# 74.net
KiCad netlist of a schematic drawn in EAGLE
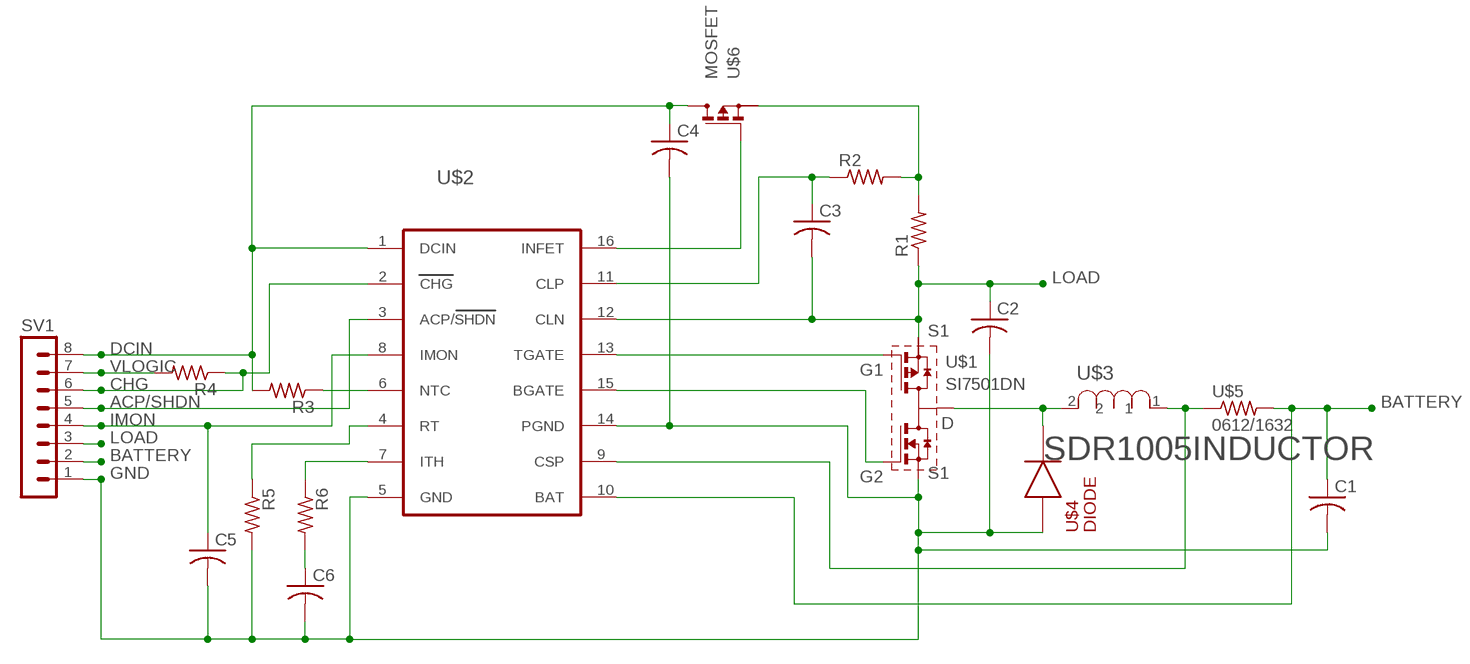
[diagram p0: schematic, sheet 1]

(export (version "E")
  (design (tool "Eeschema 10.0.6"))
  (components
    (comp (ref "C1")
      (value "C-USC1210")
      (footprint "eagle-import:C1210")
      (libsource (lib "eagle-import") (part "C-USC1210"))
    )
    (comp (ref "C2")
      (value "C-USC1210")
      (footprint "eagle-import:C1210")
      (libsource (lib "eagle-import") (part "C-USC1210"))
    )
    (comp (ref "C3")
      (value "C-USC1210")
      (footprint "eagle-import:C1210")
      (libsource (lib "eagle-import") (part "C-USC1210"))
    )
    (comp (ref "C4")
      (value "C-USC1210")
      (footprint "eagle-import:C1210")
      (libsource (lib "eagle-import") (part "C-USC1210"))
    )
    (comp (ref "C5")
      (value "C-USC1210")
      (footprint "eagle-import:C1210")
      (libsource (lib "eagle-import") (part "C-USC1210"))
    )
    (comp (ref "C6")
      (value "C-USC1210")
      (footprint "eagle-import:C1210")
      (libsource (lib "eagle-import") (part "C-USC1210"))
    )
    (comp (ref "R1")
      (value "R-US_R1206")
      (footprint "eagle-import:R1206")
      (libsource (lib "eagle-import") (part "R-US_R1206"))
    )
    (comp (ref "R2")
      (value "R-US_R1206")
      (footprint "eagle-import:R1206")
      (libsource (lib "eagle-import") (part "R-US_R1206"))
    )
    (comp (ref "R3")
      (value "R-US_R1206")
      (footprint "eagle-import:R1206")
      (libsource (lib "eagle-import") (part "R-US_R1206"))
    )
    (comp (ref "R4")
      (value "R-US_R1206")
      (footprint "eagle-import:R1206")
      (libsource (lib "eagle-import") (part "R-US_R1206"))
    )
    (comp (ref "R5")
      (value "R-US_R1206")
      (footprint "eagle-import:R1206")
      (libsource (lib "eagle-import") (part "R-US_R1206"))
    )
    (comp (ref "R6")
      (value "R-US_R1206")
      (footprint "eagle-import:R1206")
      (libsource (lib "eagle-import") (part "R-US_R1206"))
    )
    (comp (ref "SV1")
      (value "MA08-1")
      (footprint "eagle-import:MA08-1")
      (libsource (lib "eagle-import") (part "MA08-1"))
    )
    (comp (ref "U$1")
      (value "SI7501DN")
      (footprint "eagle-import:POWERPAK")
      (libsource (lib "eagle-import") (part "SI7501DN"))
    )
    (comp (ref "U$2")
      (value "LTC6004")
      (footprint "eagle-import:SSOP-16")
      (libsource (lib "eagle-import") (part "LTC6004"))
    )
    (comp (ref "U$3")
      (value "SDR1005INDUCTOR")
      (footprint "eagle-import:POWERINDUCTOR")
      (libsource (lib "eagle-import") (part "SDR1005INDUCTOR"))
    )
    (comp (ref "U$4")
      (value "DIODE")
      (footprint "eagle-import:DIODE")
      (libsource (lib "eagle-import") (part "DIODE"))
    )
    (comp (ref "U$5")
      (value "0612/1632")
      (footprint "eagle-import:0612_1632")
      (libsource (lib "eagle-import") (part "0612/1632"))
    )
    (comp (ref "U$6")
      (value "MOSFET")
      (footprint "eagle-import:SOT-23")
      (libsource (lib "eagle-import") (part "MOSFET"))
    )
  )
  (nets
    (net (code "1") (name "/ACP{slash}SHDN") (class "Default")
      (node (ref "SV1") (pin "5") (pinfunction "5_5") (pintype "passive"))
      (node (ref "U$2") (pin "3") (pinfunction "ACP/SHDN_3") (pintype "power_in"))
    )
    (net (code "2") (name "/BATTERY") (class "Default")
      (node (ref "C1") (pin "1") (pinfunction "1_1") (pintype "passive"))
      (node (ref "SV1") (pin "2") (pinfunction "2_2") (pintype "passive"))
      (node (ref "U$2") (pin "10") (pinfunction "BAT_10") (pintype "power_in"))
      (node (ref "U$5") (pin "2") (pinfunction "2_2") (pintype "passive"))
    )
    (net (code "3") (name "/CHG") (class "Default")
      (node (ref "R4") (pin "1") (pinfunction "1_1") (pintype "passive"))
      (node (ref "SV1") (pin "6") (pinfunction "6_6") (pintype "passive"))
      (node (ref "U$2") (pin "2") (pinfunction "CHG_2") (pintype "power_in"))
    )
    (net (code "4") (name "/DCIN") (class "Default")
      (node (ref "C4") (pin "1") (pinfunction "1_1") (pintype "passive"))
      (node (ref "R3") (pin "2") (pinfunction "2_2") (pintype "passive"))
      (node (ref "SV1") (pin "8") (pinfunction "8_8") (pintype "passive"))
      (node (ref "U$2") (pin "1") (pinfunction "DCIN_1") (pintype "power_in"))
      (node (ref "U$6") (pin "DRAIN") (pinfunction "D_DRAIN") (pintype "passive"))
    )
    (net (code "5") (name "/GND") (class "Default")
      (node (ref "C1") (pin "2") (pinfunction "2_2") (pintype "passive"))
      (node (ref "C2") (pin "2") (pinfunction "2_2") (pintype "passive"))
      (node (ref "C4") (pin "2") (pinfunction "2_2") (pintype "passive"))
      (node (ref "C5") (pin "2") (pinfunction "2_2") (pintype "passive"))
      (node (ref "C6") (pin "2") (pinfunction "2_2") (pintype "passive"))
      (node (ref "R5") (pin "2") (pinfunction "2_2") (pintype "passive"))
      (node (ref "SV1") (pin "1") (pinfunction "1_1") (pintype "passive"))
      (node (ref "U$1") (pin "S2") (pinfunction "S2_S2") (pintype "passive"))
      (node (ref "U$2") (pin "14") (pinfunction "PGND_14") (pintype "power_in"))
      (node (ref "U$2") (pin "5") (pinfunction "GND_5") (pintype "input"))
      (node (ref "U$4") (pin "P$1") (pinfunction "1_P$1") (pintype "bidirectional"))
    )
    (net (code "6") (name "/IMON") (class "Default")
      (node (ref "C5") (pin "1") (pinfunction "1_1") (pintype "passive"))
      (node (ref "SV1") (pin "4") (pinfunction "4_4") (pintype "passive"))
      (node (ref "U$2") (pin "8") (pinfunction "IMON_8") (pintype "power_in"))
    )
    (net (code "7") (name "/LOAD") (class "Default")
      (node (ref "C2") (pin "1") (pinfunction "1_1") (pintype "passive"))
      (node (ref "C3") (pin "2") (pinfunction "2_2") (pintype "passive"))
      (node (ref "R1") (pin "1") (pinfunction "1_1") (pintype "passive"))
      (node (ref "SV1") (pin "3") (pinfunction "3_3") (pintype "passive"))
      (node (ref "U$1") (pin "S1") (pinfunction "S1_S1") (pintype "passive"))
      (node (ref "U$2") (pin "12") (pinfunction "CLN_12") (pintype "power_in"))
    )
    (net (code "8") (name "/VLOGIC") (class "Default")
      (node (ref "R4") (pin "2") (pinfunction "2_2") (pintype "passive"))
      (node (ref "SV1") (pin "7") (pinfunction "7_7") (pintype "passive"))
    )
    (net (code "9") (name "Net-(C6-Pad1)") (class "Default")
      (node (ref "C6") (pin "1") (pinfunction "1_1") (pintype "passive"))
      (node (ref "R6") (pin "2") (pinfunction "2_2") (pintype "passive"))
    )
    (net (code "10") (name "Net-(U$2-BGATE)") (class "Default")
      (node (ref "U$1") (pin "G2") (pinfunction "G2_G2") (pintype "passive"))
      (node (ref "U$2") (pin "15") (pinfunction "BGATE_15") (pintype "power_in"))
    )
    (net (code "11") (name "Net-(U$2-CLP)") (class "Default")
      (node (ref "C3") (pin "1") (pinfunction "1_1") (pintype "passive"))
      (node (ref "R2") (pin "1") (pinfunction "1_1") (pintype "passive"))
      (node (ref "U$2") (pin "11") (pinfunction "CLP_11") (pintype "output"))
    )
    (net (code "12") (name "Net-(U$2-CSP)") (class "Default")
      (node (ref "U$2") (pin "9") (pinfunction "CSP_9") (pintype "power_in"))
      (node (ref "U$3") (pin "1") (pinfunction "1_1") (pintype "passive"))
      (node (ref "U$5") (pin "1") (pinfunction "1_1") (pintype "passive"))
    )
    (net (code "13") (name "Net-(U$2-INFET)") (class "Default")
      (node (ref "U$2") (pin "16") (pinfunction "INFET_16") (pintype "output"))
      (node (ref "U$6") (pin "GATE") (pinfunction "G_GATE") (pintype "passive"))
    )
    (net (code "14") (name "Net-(U$2-ITH)") (class "Default")
      (node (ref "R6") (pin "1") (pinfunction "1_1") (pintype "passive"))
      (node (ref "U$2") (pin "7") (pinfunction "ITH_7") (pintype "input"))
    )
    (net (code "15") (name "Net-(U$2-NTC)") (class "Default")
      (node (ref "R3") (pin "1") (pinfunction "1_1") (pintype "passive"))
      (node (ref "U$2") (pin "6") (pinfunction "NTC_6") (pintype "power_in"))
    )
    (net (code "16") (name "Net-(U$2-RT)") (class "Default")
      (node (ref "R5") (pin "1") (pinfunction "1_1") (pintype "passive"))
      (node (ref "U$2") (pin "4") (pinfunction "RT_4") (pintype "input"))
    )
    (net (code "17") (name "Net-(U$2-TGATE)") (class "Default")
      (node (ref "U$1") (pin "G1") (pinfunction "G1_G1") (pintype "passive"))
      (node (ref "U$2") (pin "13") (pinfunction "TGATE_13") (pintype "input"))
    )
    (net (code "18") (name "Net-(U$4-2)") (class "Default")
      (node (ref "U$1") (pin "D") (pinfunction "D_D") (pintype "passive"))
      (node (ref "U$3") (pin "2") (pinfunction "2_2") (pintype "passive"))
      (node (ref "U$4") (pin "P$2") (pinfunction "2_P$2") (pintype "bidirectional"))
    )
    (net (code "19") (name "Net-(U$6-S)") (class "Default")
      (node (ref "R1") (pin "2") (pinfunction "2_2") (pintype "passive"))
      (node (ref "R2") (pin "2") (pinfunction "2_2") (pintype "passive"))
      (node (ref "U$6") (pin "SOURCE") (pinfunction "S_SOURCE") (pintype "passive"))
    )
  )
)
